# LinearA_2017_4L_1.net
KiCad netlist of a schematic drawn in EAGLE
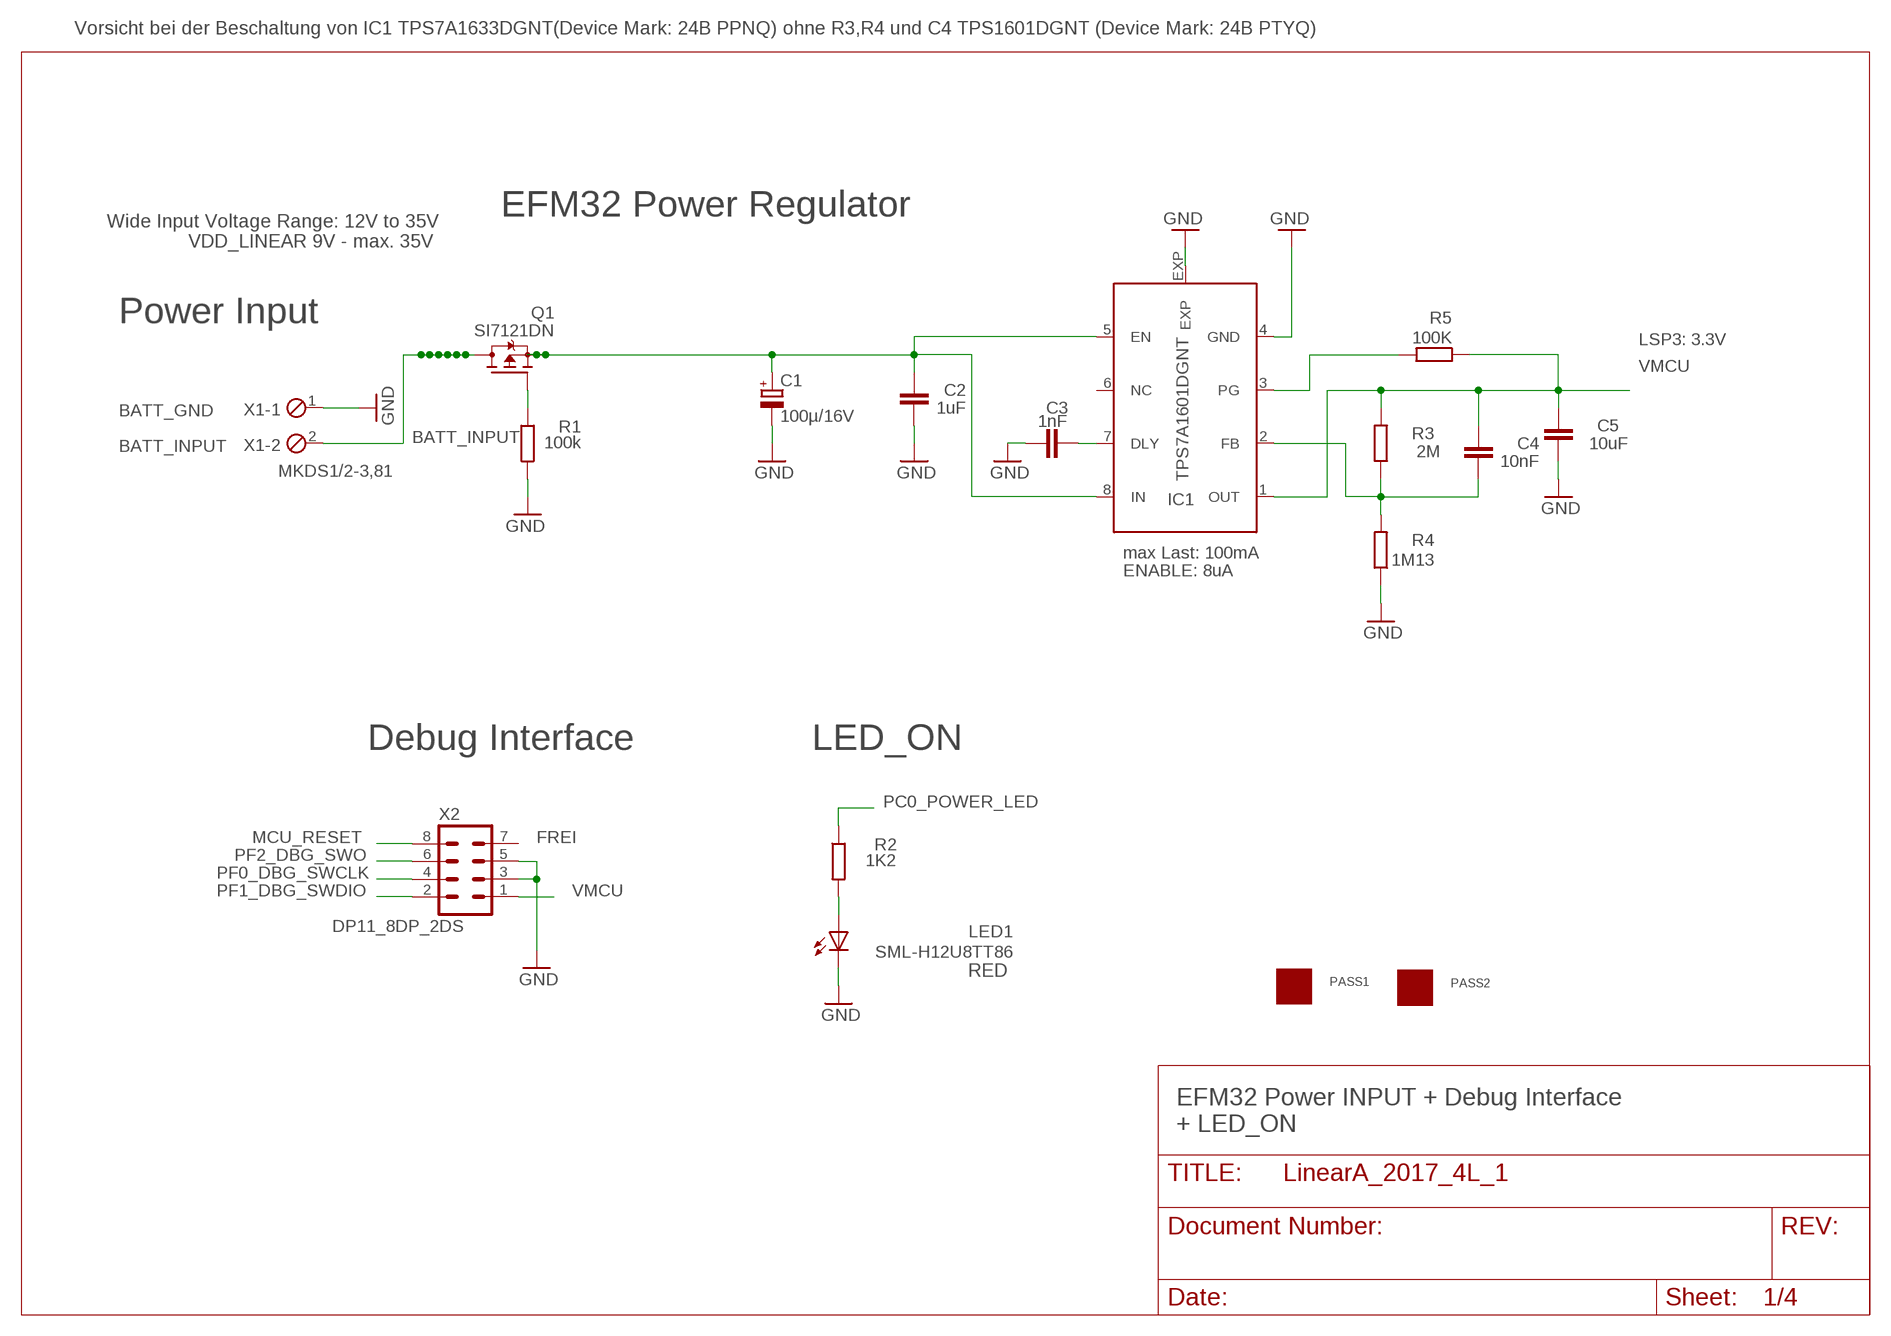
[diagram p0: schematic, sheet 1]
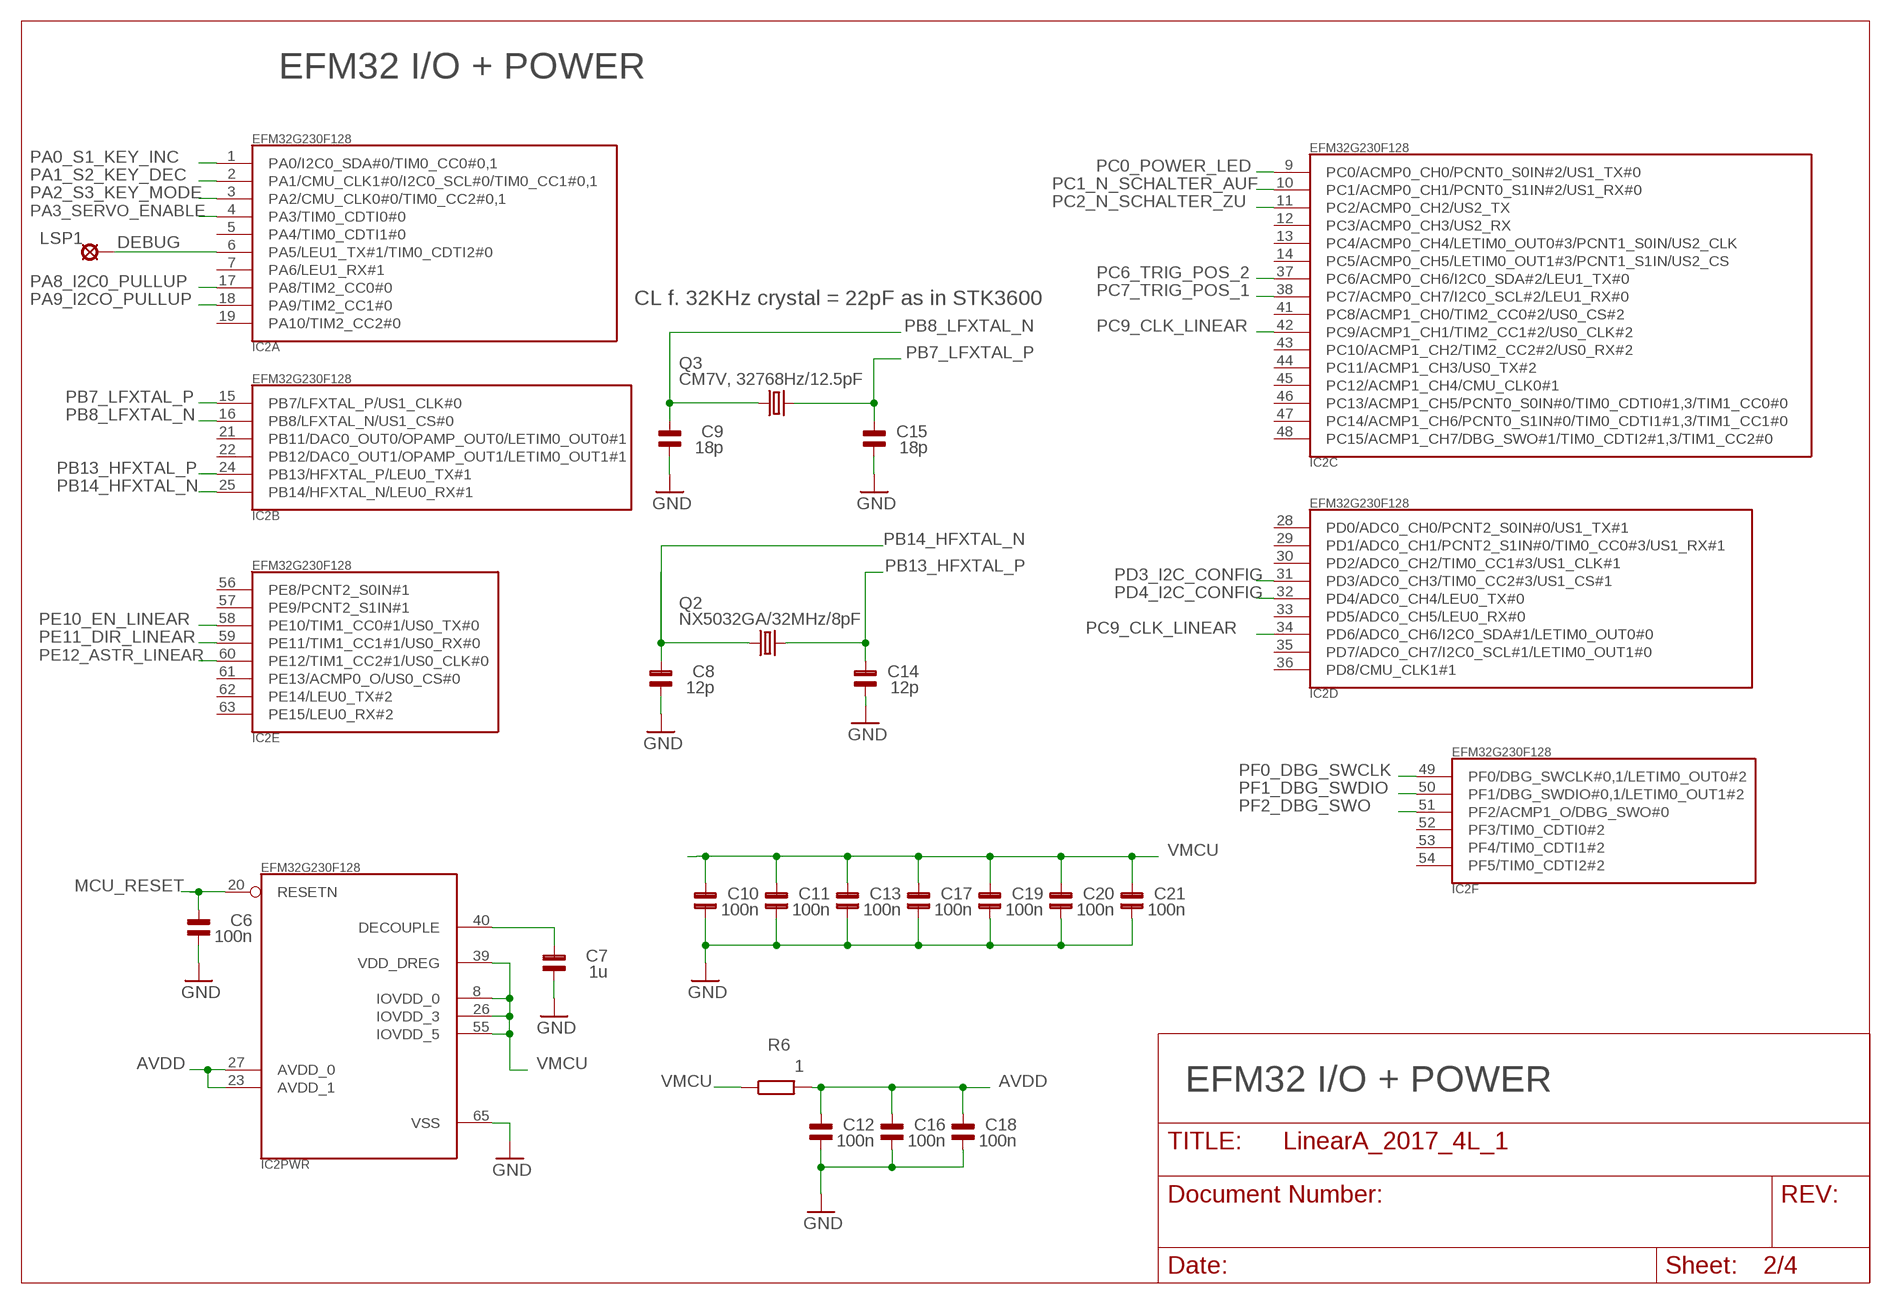
[diagram p1: schematic, sheet 2]
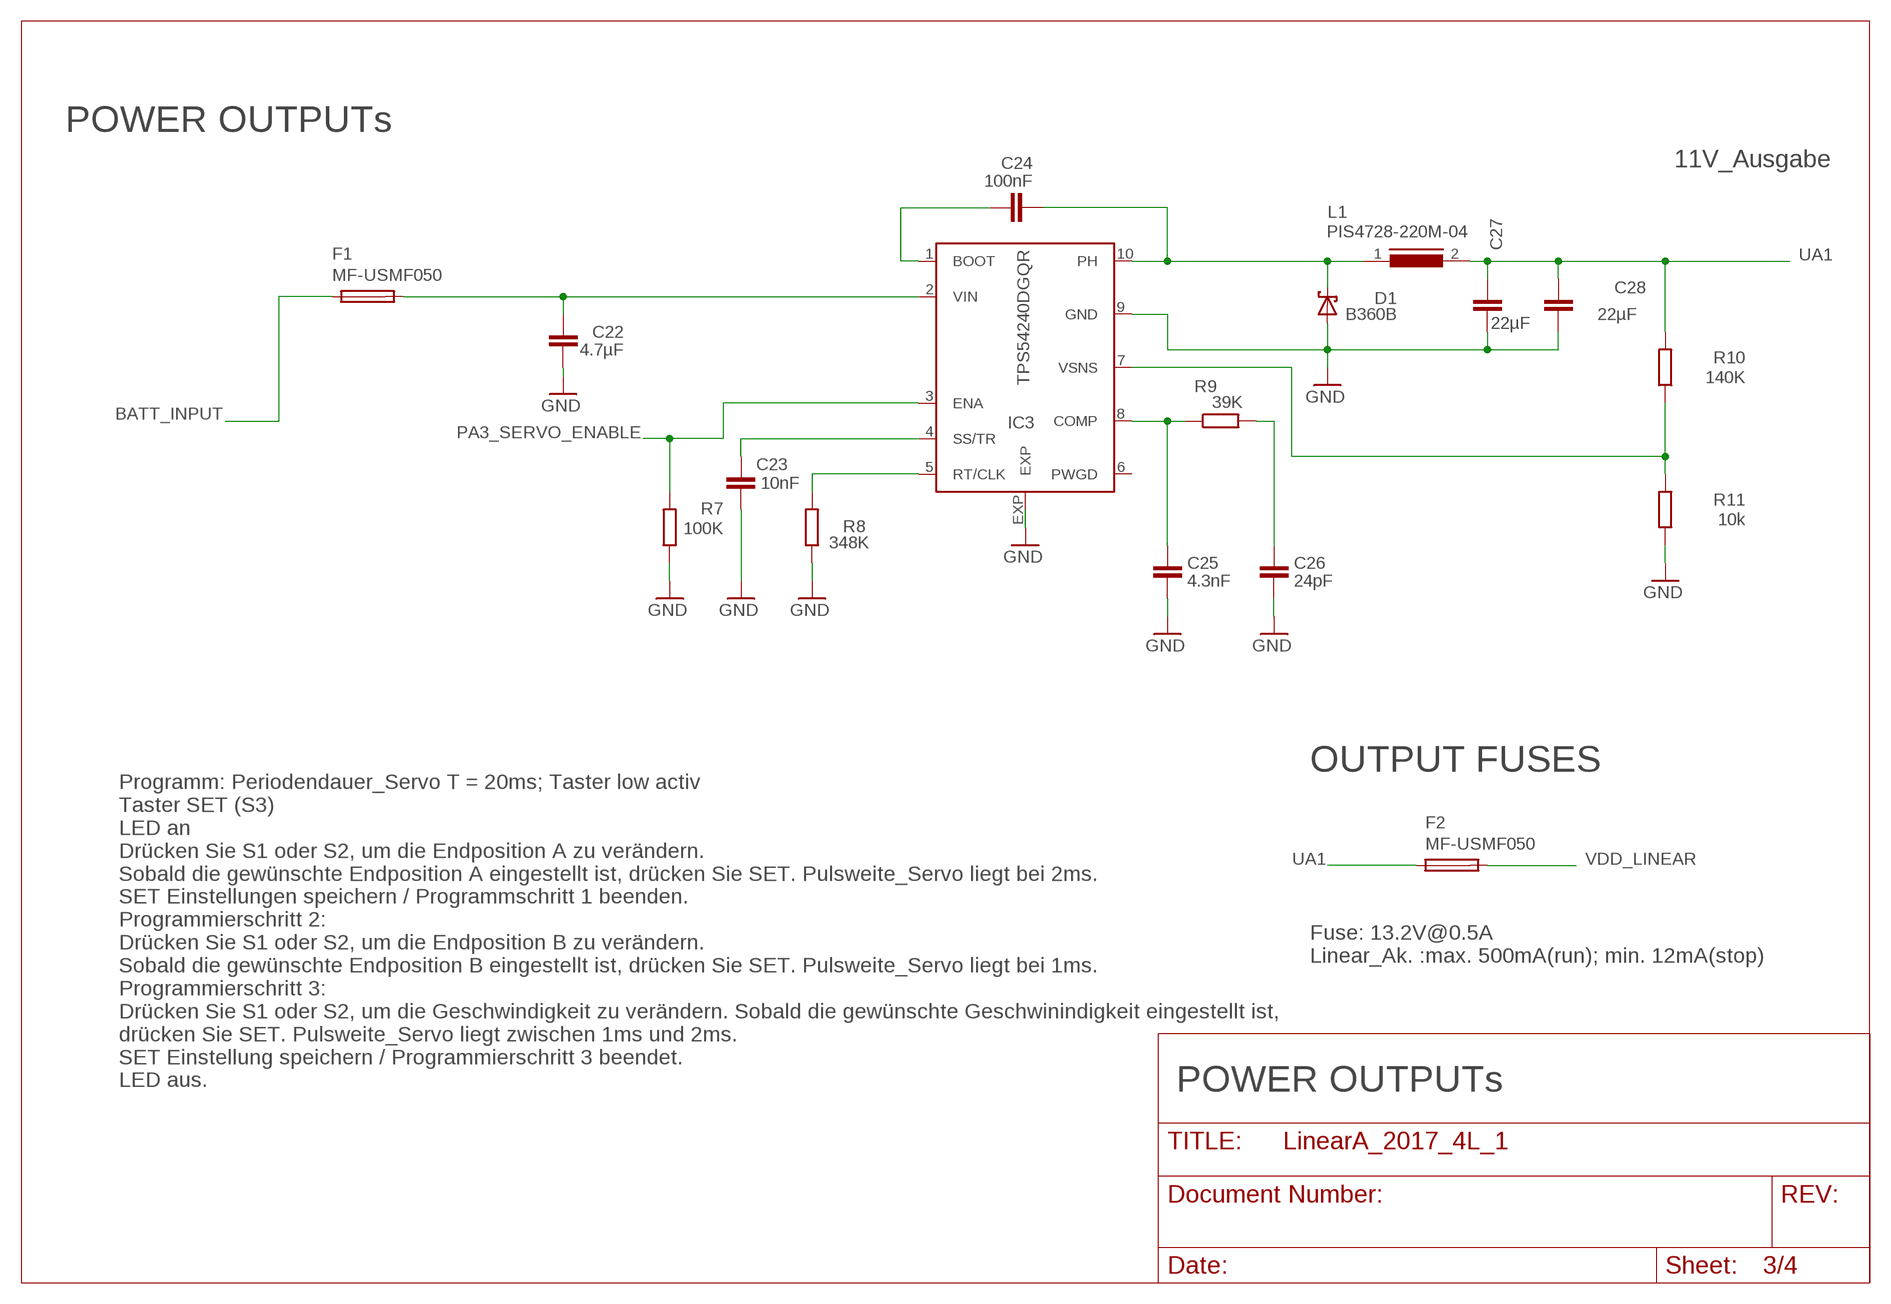
[diagram p2: schematic, sheet 3]
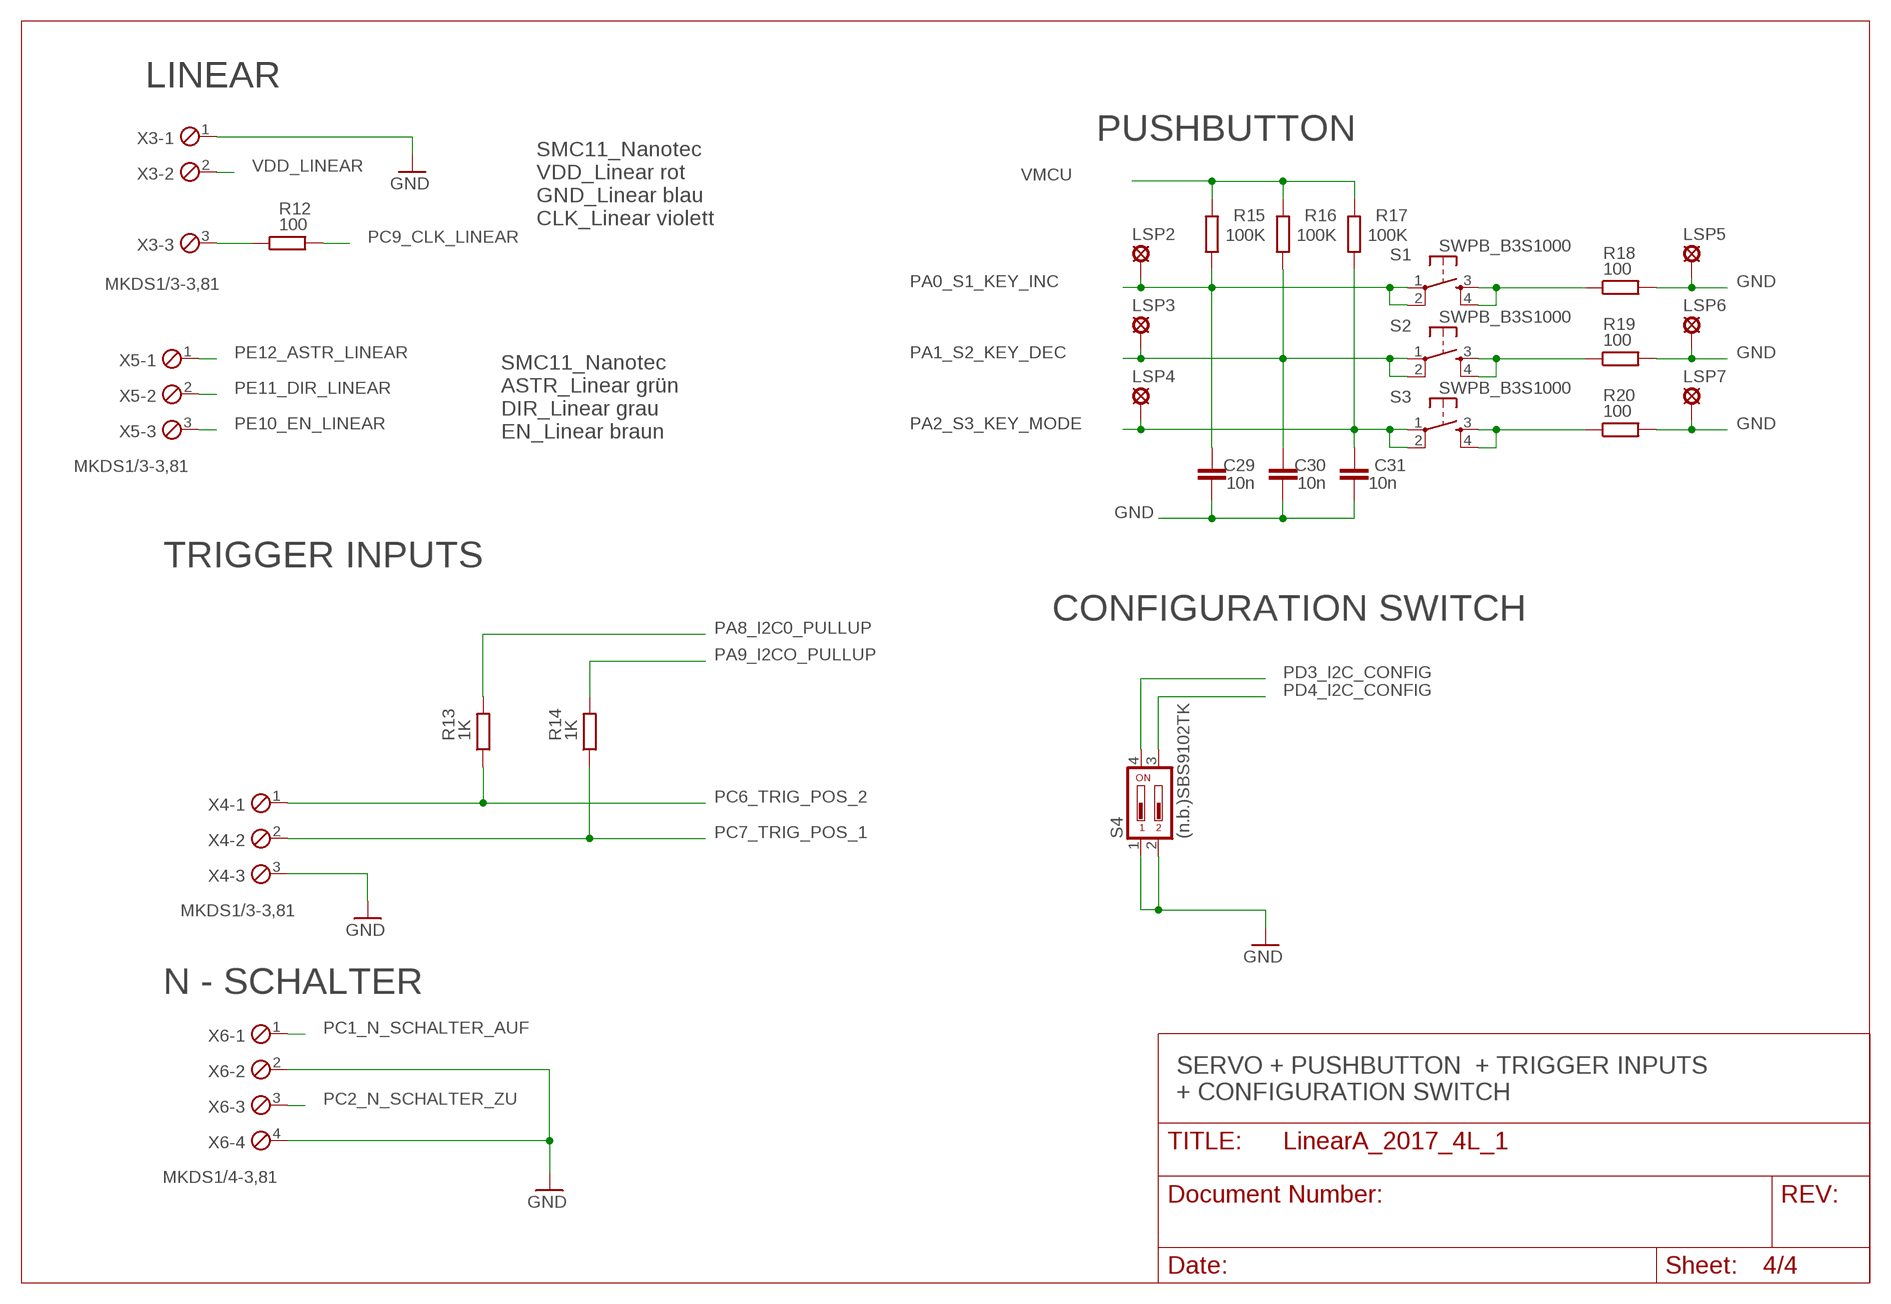
[diagram p3: schematic, sheet 4]

(export (version "E")
  (design (tool "Eeschema 10.0.6"))
  (components
    (comp (ref "C6")
      (value "100n")
      (footprint "eagle-import:0805")
      (libsource (lib "eagle-import") (part "C_SMD0805"))
    )
    (comp (ref "C7")
      (value "1u")
      (footprint "eagle-import:0805")
      (libsource (lib "eagle-import") (part "C_SMD0805"))
    )
    (comp (ref "C8")
      (value "12p")
      (footprint "eagle-import:0805")
      (libsource (lib "eagle-import") (part "C_SMD0805"))
    )
    (comp (ref "C9")
      (value "18p")
      (footprint "eagle-import:0805")
      (libsource (lib "eagle-import") (part "C_SMD0805"))
    )
    (comp (ref "C10")
      (value "100n")
      (footprint "eagle-import:0805")
      (libsource (lib "eagle-import") (part "C_SMD0805"))
    )
    (comp (ref "C11")
      (value "100n")
      (footprint "eagle-import:0805")
      (libsource (lib "eagle-import") (part "C_SMD0805"))
    )
    (comp (ref "C12")
      (value "100n")
      (footprint "eagle-import:0805")
      (libsource (lib "eagle-import") (part "C_SMD0805"))
    )
    (comp (ref "C13")
      (value "100n")
      (footprint "eagle-import:0805")
      (libsource (lib "eagle-import") (part "C_SMD0805"))
    )
    (comp (ref "C14")
      (value "12p")
      (footprint "eagle-import:0805")
      (libsource (lib "eagle-import") (part "C_SMD0805"))
    )
    (comp (ref "C15")
      (value "18p")
      (footprint "eagle-import:0805")
      (libsource (lib "eagle-import") (part "C_SMD0805"))
    )
    (comp (ref "C16")
      (value "100n")
      (footprint "eagle-import:0805")
      (libsource (lib "eagle-import") (part "C_SMD0805"))
    )
    (comp (ref "C17")
      (value "100n")
      (footprint "eagle-import:0805")
      (libsource (lib "eagle-import") (part "C_SMD0805"))
    )
    (comp (ref "C18")
      (value "100n")
      (footprint "eagle-import:0805")
      (libsource (lib "eagle-import") (part "C_SMD0805"))
    )
    (comp (ref "C19")
      (value "100n")
      (footprint "eagle-import:0805")
      (libsource (lib "eagle-import") (part "C_SMD0805"))
    )
    (comp (ref "C20")
      (value "100n")
      (footprint "eagle-import:0805")
      (libsource (lib "eagle-import") (part "C_SMD0805"))
    )
    (comp (ref "C21")
      (value "100n")
      (footprint "eagle-import:0805")
      (libsource (lib "eagle-import") (part "C_SMD0805"))
    )
    (comp (ref "IC2")
      (value "EFM32G230F128")
      (footprint "eagle-import:QFN64")
      (libsource (lib "eagle-import") (part "EFM32G230F128"))
    )
    (comp (ref "LSP1")
      (value "(n.b.)LSP10")
      (footprint "eagle-import:LSP10")
      (libsource (lib "eagle-import") (part "LSP10"))
    )
    (comp (ref "Q2")
      (value "NX5032GA/32MHz/8pF")
      (footprint "eagle-import:CRYSTAL2P5.0X3.2")
      (libsource (lib "eagle-import") (part "CRYSTAL2P5.0X3.2"))
    )
    (comp (ref "Q3")
      (value "CM7V, 32768Hz/12.5pF")
      (footprint "eagle-import:CRYSTAL2P3.2X1.5")
      (libsource (lib "eagle-import") (part "CRYSTAL2P"))
    )
    (comp (ref "R6")
      (value "1")
      (footprint "eagle-import:R0805")
      (libsource (lib "eagle-import") (part "R-EU_R0805"))
    )
    (comp (ref "C29")
      (value "10n")
      (footprint "eagle-import:C0603")
      (libsource (lib "eagle-import") (part "resistor_C-EUC0603"))
    )
    (comp (ref "C30")
      (value "10n")
      (footprint "eagle-import:C0603")
      (libsource (lib "eagle-import") (part "resistor_C-EUC0603"))
    )
    (comp (ref "C31")
      (value "10n")
      (footprint "eagle-import:C0603")
      (libsource (lib "eagle-import") (part "resistor_C-EUC0603"))
    )
    (comp (ref "LSP2")
      (value "(n.b.)LSP10")
      (footprint "eagle-import:LSP10")
      (libsource (lib "eagle-import") (part "LSP10"))
    )
    (comp (ref "LSP3")
      (value "(n.b.)LSP10")
      (footprint "eagle-import:LSP10")
      (libsource (lib "eagle-import") (part "LSP10"))
    )
    (comp (ref "LSP4")
      (value "(n.b.)LSP10")
      (footprint "eagle-import:LSP10")
      (libsource (lib "eagle-import") (part "LSP10"))
    )
    (comp (ref "LSP5")
      (value "(n.b.)LSP10")
      (footprint "eagle-import:LSP10")
      (libsource (lib "eagle-import") (part "LSP10"))
    )
    (comp (ref "LSP6")
      (value "(n.b.)LSP10")
      (footprint "eagle-import:LSP10")
      (libsource (lib "eagle-import") (part "LSP10"))
    )
    (comp (ref "LSP7")
      (value "(n.b.)LSP10")
      (footprint "eagle-import:LSP10")
      (libsource (lib "eagle-import") (part "LSP10"))
    )
    (comp (ref "R12")
      (value "100")
      (footprint "eagle-import:R0805")
      (libsource (lib "eagle-import") (part "resistor_R-EU_R0805"))
    )
    (comp (ref "R13")
      (value "1K")
      (footprint "eagle-import:R0805")
      (libsource (lib "eagle-import") (part "resistor_R-EU_R0805"))
    )
    (comp (ref "R14")
      (value "1K")
      (footprint "eagle-import:R0805")
      (libsource (lib "eagle-import") (part "resistor_R-EU_R0805"))
    )
    (comp (ref "R15")
      (value "100K")
      (footprint "eagle-import:R0805")
      (libsource (lib "eagle-import") (part "resistor_R-EU_R0805"))
    )
    (comp (ref "R16")
      (value "100K")
      (footprint "eagle-import:R0805")
      (libsource (lib "eagle-import") (part "resistor_R-EU_R0805"))
    )
    (comp (ref "R17")
      (value "100K")
      (footprint "eagle-import:R0805")
      (libsource (lib "eagle-import") (part "resistor_R-EU_R0805"))
    )
    (comp (ref "R18")
      (value "100")
      (footprint "eagle-import:R0805")
      (libsource (lib "eagle-import") (part "resistor_R-EU_R0805"))
    )
    (comp (ref "R19")
      (value "100")
      (footprint "eagle-import:R0805")
      (libsource (lib "eagle-import") (part "resistor_R-EU_R0805"))
    )
    (comp (ref "R20")
      (value "100")
      (footprint "eagle-import:R0805")
      (libsource (lib "eagle-import") (part "resistor_R-EU_R0805"))
    )
    (comp (ref "S1")
      (value "SWPB_B3S1000")
      (footprint "eagle-import:DTSM-6")
      (libsource (lib "eagle-import") (part "DTSM-6"))
    )
    (comp (ref "S2")
      (value "SWPB_B3S1000")
      (footprint "eagle-import:DTSM-6")
      (libsource (lib "eagle-import") (part "DTSM-6"))
    )
    (comp (ref "S3")
      (value "SWPB_B3S1000")
      (footprint "eagle-import:DTSM-6")
      (libsource (lib "eagle-import") (part "DTSM-6"))
    )
    (comp (ref "S4")
      (value "(n.b.)SBS9102TK")
      (footprint "eagle-import:CTS-219-02")
      (libsource (lib "eagle-import") (part "219-02"))
    )
    (comp (ref "X3")
      (value "MKDS1/3-3,81")
      (footprint "eagle-import:3POL381")
      (libsource (lib "eagle-import") (part "MKDS1/3-3,81"))
    )
    (comp (ref "X4")
      (value "MKDS1/3-3,81")
      (footprint "eagle-import:3POL381")
      (libsource (lib "eagle-import") (part "MKDS1/3-3,81"))
    )
    (comp (ref "X5")
      (value "MKDS1/3-3,81")
      (footprint "eagle-import:3POL381")
      (libsource (lib "eagle-import") (part "MKDS1/3-3,81"))
    )
    (comp (ref "X6")
      (value "MKDS1/4-3,81")
      (footprint "eagle-import:4POL381")
      (libsource (lib "eagle-import") (part "MKDS1/4-3,81"))
    )
    (comp (ref "C22")
      (value "4.7µF")
      (footprint "eagle-import:C1210")
      (libsource (lib "eagle-import") (part "C-EUC1210"))
    )
    (comp (ref "C23")
      (value "10nF")
      (footprint "eagle-import:C0603")
      (libsource (lib "eagle-import") (part "C-EUC0603"))
    )
    (comp (ref "C24")
      (value "100nF")
      (footprint "eagle-import:C0603")
      (libsource (lib "eagle-import") (part "C-EUC0603"))
    )
    (comp (ref "C25")
      (value "4.3nF")
      (footprint "eagle-import:C0603")
      (libsource (lib "eagle-import") (part "C-EUC0603"))
    )
    (comp (ref "C26")
      (value "24pF")
      (footprint "eagle-import:C0603")
      (libsource (lib "eagle-import") (part "C-EUC0603"))
    )
    (comp (ref "C27")
      (value "22µF")
      (footprint "eagle-import:C1210")
      (libsource (lib "eagle-import") (part "C-EUC1210"))
    )
    (comp (ref "C28")
      (value "22µF")
      (footprint "eagle-import:C1210")
      (libsource (lib "eagle-import") (part "C-EUC1210"))
    )
    (comp (ref "D1")
      (value "B360B")
      (footprint "eagle-import:SMB")
      (libsource (lib "eagle-import") (part "SCHOTTKY-DIODESMD"))
    )
    (comp (ref "F1")
      (value "MF-USMF050")
      (footprint "eagle-import:PFUF_1210POLY")
      (libsource (lib "eagle-import") (part "PFUF"))
    )
    (comp (ref "F2")
      (value "MF-USMF050")
      (footprint "eagle-import:PFUF_1210POLY")
      (libsource (lib "eagle-import") (part "PFUF"))
    )
    (comp (ref "IC3")
      (value "TPS54240DGQR")
      (footprint "eagle-import:S-PDSO-G10")
      (libsource (lib "eagle-import") (part "TPS54240DGQR"))
    )
    (comp (ref "L1")
      (value "PIS4728-220M-04")
      (footprint "eagle-import:DR127")
      (libsource (lib "eagle-import") (part "DR127"))
    )
    (comp (ref "R7")
      (value "100K")
      (footprint "eagle-import:R0805")
      (libsource (lib "eagle-import") (part "resistor_R-EU_R0805"))
    )
    (comp (ref "R8")
      (value "348K")
      (footprint "eagle-import:R0805")
      (libsource (lib "eagle-import") (part "resistor_R-EU_R0805"))
    )
    (comp (ref "R9")
      (value "39K")
      (footprint "eagle-import:R0805")
      (libsource (lib "eagle-import") (part "resistor_R-EU_R0805"))
    )
    (comp (ref "R10")
      (value "140K")
      (footprint "eagle-import:R0805")
      (libsource (lib "eagle-import") (part "resistor_R-EU_R0805"))
    )
    (comp (ref "R11")
      (value "10k")
      (footprint "eagle-import:R0805")
      (libsource (lib "eagle-import") (part "resistor_R-EU_R0805"))
    )
    (comp (ref "C1")
      (value "100µ/16V")
      (footprint "eagle-import:PANASONIC_E")
      (libsource (lib "eagle-import") (part "CPOL-EUE"))
    )
    (comp (ref "C2")
      (value "1uF")
      (footprint "eagle-import:C0603")
      (libsource (lib "eagle-import") (part "resistor_C-EUC0603"))
    )
    (comp (ref "C3")
      (value "1nF")
      (footprint "eagle-import:C0603")
      (libsource (lib "eagle-import") (part "resistor_C-EUC0603"))
    )
    (comp (ref "C4")
      (value "10nF")
      (footprint "eagle-import:C0603")
      (libsource (lib "eagle-import") (part "resistor_C-EUC0603"))
    )
    (comp (ref "C5")
      (value "10uF")
      (footprint "eagle-import:C1206")
      (libsource (lib "eagle-import") (part "resistor_C-EUC1206"))
    )
    (comp (ref "IC1")
      (value "TPS7A1601DGNT")
      (footprint "eagle-import:DGN_S-PDSO-G8-EXP")
      (libsource (lib "eagle-import") (part "TPS7A16"))
    )
    (comp (ref "LED1")
      (value "SML-H12U8TT86")
      (footprint "eagle-import:CHIPLED_0805")
      (libsource (lib "eagle-import") (part "LEDCHIPLED_0805"))
    )
    (comp (ref "PASS1")
      (value "ROUND_1MM1.5")
      (footprint "eagle-import:ROUND2_1.5MM")
      (libsource (lib "eagle-import") (part "ROUND_1MM1.5"))
    )
    (comp (ref "PASS2")
      (value "ROUND_1MM1.5")
      (footprint "eagle-import:ROUND2_1.5MM")
      (libsource (lib "eagle-import") (part "ROUND_1MM1.5"))
    )
    (comp (ref "Q1")
      (value "SI7121DN")
      (footprint "eagle-import:TRANSISTOR-FET_1212-8S")
      (libsource (lib "eagle-import") (part "TRANSISTOR-FET_SI7113DN"))
    )
    (comp (ref "R1")
      (value "100k")
      (footprint "eagle-import:R0805")
      (libsource (lib "eagle-import") (part "resistor_R-EU_R0805"))
    )
    (comp (ref "R2")
      (value "1K2")
      (footprint "eagle-import:R0805")
      (libsource (lib "eagle-import") (part "resistor_R-EU_R0805"))
    )
    (comp (ref "R3")
      (value "2M")
      (footprint "eagle-import:R0805")
      (libsource (lib "eagle-import") (part "resistor_R-EU_R0805"))
    )
    (comp (ref "R4")
      (value "1M13")
      (footprint "eagle-import:R0805")
      (libsource (lib "eagle-import") (part "resistor_R-EU_R0805"))
    )
    (comp (ref "R5")
      (value "100K")
      (footprint "eagle-import:R0805")
      (libsource (lib "eagle-import") (part "resistor_R-EU_R0805"))
    )
    (comp (ref "X1")
      (value "MKDS1/2-3,81")
      (footprint "eagle-import:2POL381")
      (libsource (lib "eagle-import") (part "MKDS1/2-3,81"))
    )
    (comp (ref "X2")
      (value "DP11_8DP_2DS")
      (footprint "eagle-import:DP11_8DP-2DS")
      (libsource (lib "eagle-import") (part "DP11_8DP_2DS"))
    )
  )
  (nets
    (net (code "1") (name "AVDD") (class "Default")
      (node (ref "C12") (pin "2") (pinfunction "2_2") (pintype "passive"))
      (node (ref "C16") (pin "2") (pinfunction "2_2") (pintype "passive"))
      (node (ref "C18") (pin "2") (pinfunction "2_2") (pintype "passive"))
      (node (ref "IC2") (pin "23") (pinfunction "AVDD_1_23") (pintype "power_in"))
      (node (ref "IC2") (pin "27") (pinfunction "AVDD_0_27") (pintype "power_in"))
      (node (ref "R6") (pin "2") (pinfunction "2_2") (pintype "passive"))
    )
    (net (code "2") (name "BATT_INPUT") (class "Default")
      (node (ref "F1") (pin "P$1") (pinfunction "1_P$1") (pintype "passive"))
      (node (ref "Q1") (pin "10") (pinfunction "D_10") (pintype "passive"))
      (node (ref "Q1") (pin "11") (pinfunction "D_11") (pintype "passive"))
      (node (ref "Q1") (pin "5") (pinfunction "D_5") (pintype "passive"))
      (node (ref "Q1") (pin "6") (pinfunction "D_6") (pintype "passive"))
      (node (ref "Q1") (pin "7") (pinfunction "D_7") (pintype "passive"))
      (node (ref "Q1") (pin "8") (pinfunction "D_8") (pintype "passive"))
      (node (ref "Q1") (pin "9") (pinfunction "D_9") (pintype "passive"))
      (node (ref "X1") (pin "2") (pinfunction "1_2") (pintype "passive"))
    )
    (net (code "3") (name "DEBUG") (class "Default")
      (node (ref "IC2") (pin "6") (pinfunction "PA5/LEU1_TX#1/TIM0_CDTI2#0_6") (pintype "bidirectional"))
      (node (ref "LSP1") (pin "MP") (pinfunction "MP_MP") (pintype "passive"))
    )
    (net (code "4") (name "GND") (class "Default")
      (node (ref "C1") (pin "-") (pinfunction "-_-") (pintype "passive"))
      (node (ref "C10") (pin "1") (pinfunction "1_1") (pintype "passive"))
      (node (ref "C11") (pin "1") (pinfunction "1_1") (pintype "passive"))
      (node (ref "C12") (pin "1") (pinfunction "1_1") (pintype "passive"))
      (node (ref "C13") (pin "1") (pinfunction "1_1") (pintype "passive"))
      (node (ref "C14") (pin "1") (pinfunction "1_1") (pintype "passive"))
      (node (ref "C15") (pin "1") (pinfunction "1_1") (pintype "passive"))
      (node (ref "C16") (pin "1") (pinfunction "1_1") (pintype "passive"))
      (node (ref "C17") (pin "1") (pinfunction "1_1") (pintype "passive"))
      (node (ref "C18") (pin "1") (pinfunction "1_1") (pintype "passive"))
      (node (ref "C19") (pin "1") (pinfunction "1_1") (pintype "passive"))
      (node (ref "C2") (pin "1") (pinfunction "1_1") (pintype "passive"))
      (node (ref "C20") (pin "1") (pinfunction "1_1") (pintype "passive"))
      (node (ref "C21") (pin "1") (pinfunction "1_1") (pintype "passive"))
      (node (ref "C22") (pin "2") (pinfunction "2_2") (pintype "passive"))
      (node (ref "C23") (pin "2") (pinfunction "2_2") (pintype "passive"))
      (node (ref "C25") (pin "2") (pinfunction "2_2") (pintype "passive"))
      (node (ref "C26") (pin "2") (pinfunction "2_2") (pintype "passive"))
      (node (ref "C27") (pin "2") (pinfunction "2_2") (pintype "passive"))
      (node (ref "C28") (pin "2") (pinfunction "2_2") (pintype "passive"))
      (node (ref "C29") (pin "1") (pinfunction "1_1") (pintype "passive"))
      (node (ref "C3") (pin "1") (pinfunction "1_1") (pintype "passive"))
      (node (ref "C30") (pin "1") (pinfunction "1_1") (pintype "passive"))
      (node (ref "C31") (pin "1") (pinfunction "1_1") (pintype "passive"))
      (node (ref "C5") (pin "1") (pinfunction "1_1") (pintype "passive"))
      (node (ref "C6") (pin "1") (pinfunction "1_1") (pintype "passive"))
      (node (ref "C7") (pin "1") (pinfunction "1_1") (pintype "passive"))
      (node (ref "C8") (pin "1") (pinfunction "1_1") (pintype "passive"))
      (node (ref "C9") (pin "1") (pinfunction "1_1") (pintype "passive"))
      (node (ref "D1") (pin "A") (pinfunction "A_A") (pintype "passive"))
      (node (ref "IC1") (pin "4") (pinfunction "GND_4") (pintype "passive"))
      (node (ref "IC1") (pin "EXP") (pinfunction "EXP_EXP") (pintype "passive"))
      (node (ref "IC2") (pin "65") (pinfunction "VSS_65") (pintype "power_in"))
      (node (ref "IC3") (pin "9") (pinfunction "GND_9") (pintype "power_in"))
      (node (ref "IC3") (pin "EXP") (pinfunction "EXP_EXP") (pintype "power_in"))
      (node (ref "LED1") (pin "C") (pinfunction "C_C") (pintype "passive"))
      (node (ref "LSP5") (pin "MP") (pinfunction "MP_MP") (pintype "passive"))
      (node (ref "LSP6") (pin "MP") (pinfunction "MP_MP") (pintype "passive"))
      (node (ref "LSP7") (pin "MP") (pinfunction "MP_MP") (pintype "passive"))
      (node (ref "R1") (pin "1") (pinfunction "1_1") (pintype "passive"))
      (node (ref "R11") (pin "1") (pinfunction "1_1") (pintype "passive"))
      (node (ref "R18") (pin "2") (pinfunction "2_2") (pintype "passive"))
      (node (ref "R19") (pin "2") (pinfunction "2_2") (pintype "passive"))
      (node (ref "R20") (pin "2") (pinfunction "2_2") (pintype "passive"))
      (node (ref "R4") (pin "1") (pinfunction "1_1") (pintype "passive"))
      (node (ref "R7") (pin "1") (pinfunction "1_1") (pintype "passive"))
      (node (ref "R8") (pin "1") (pinfunction "1_1") (pintype "passive"))
      (node (ref "S4") (pin "1") (pinfunction "1_1") (pintype "passive"))
      (node (ref "S4") (pin "2") (pinfunction "2_2") (pintype "passive"))
      (node (ref "X1") (pin "1") (pinfunction "1_1") (pintype "passive"))
      (node (ref "X2") (pin "3") (pinfunction "3_3") (pintype "passive"))
      (node (ref "X2") (pin "5") (pinfunction "5_5") (pintype "passive"))
      (node (ref "X3") (pin "1") (pinfunction "1_1") (pintype "passive"))
      (node (ref "X4") (pin "3") (pinfunction "1_3") (pintype "passive"))
      (node (ref "X6") (pin "2") (pinfunction "1_2") (pintype "passive"))
      (node (ref "X6") (pin "4") (pinfunction "1_4") (pintype "passive"))
    )
    (net (code "5") (name "MCU_RESET") (class "Default")
      (node (ref "C6") (pin "2") (pinfunction "2_2") (pintype "passive"))
      (node (ref "IC2") (pin "20") (pinfunction "RESETN_20") (pintype "passive"))
      (node (ref "X2") (pin "8") (pinfunction "8_8") (pintype "passive"))
    )
    (net (code "6") (name "Net-(C26-Pad1)") (class "Default")
      (node (ref "C26") (pin "1") (pinfunction "1_1") (pintype "passive"))
      (node (ref "R9") (pin "2") (pinfunction "2_2") (pintype "passive"))
    )
    (net (code "7") (name "Net-(F1-2)") (class "Default")
      (node (ref "C22") (pin "1") (pinfunction "1_1") (pintype "passive"))
      (node (ref "F1") (pin "P$2") (pinfunction "2_P$2") (pintype "passive"))
      (node (ref "IC3") (pin "2") (pinfunction "VIN_2") (pintype "input"))
    )
    (net (code "8") (name "Net-(IC1-DLY)") (class "Default")
      (node (ref "C3") (pin "2") (pinfunction "2_2") (pintype "passive"))
      (node (ref "IC1") (pin "7") (pinfunction "DLY_7") (pintype "output"))
    )
    (net (code "9") (name "Net-(IC1-EN)") (class "Default")
      (node (ref "C1") (pin "+") (pinfunction "+_+") (pintype "passive"))
      (node (ref "C2") (pin "2") (pinfunction "2_2") (pintype "passive"))
      (node (ref "IC1") (pin "5") (pinfunction "EN_5") (pintype "input"))
      (node (ref "IC1") (pin "8") (pinfunction "IN_8") (pintype "passive"))
      (node (ref "Q1") (pin "1") (pinfunction "S_1") (pintype "passive"))
      (node (ref "Q1") (pin "2") (pinfunction "S_2") (pintype "passive"))
      (node (ref "Q1") (pin "3") (pinfunction "S_3") (pintype "passive"))
    )
    (net (code "10") (name "Net-(IC1-FB)") (class "Default")
      (node (ref "C4") (pin "1") (pinfunction "1_1") (pintype "passive"))
      (node (ref "IC1") (pin "2") (pinfunction "FB_2") (pintype "input"))
      (node (ref "R3") (pin "1") (pinfunction "1_1") (pintype "passive"))
      (node (ref "R4") (pin "2") (pinfunction "2_2") (pintype "passive"))
    )
    (net (code "11") (name "Net-(IC1-PG)") (class "Default")
      (node (ref "IC1") (pin "3") (pinfunction "PG_3") (pintype "output"))
      (node (ref "R5") (pin "2") (pinfunction "2_2") (pintype "passive"))
    )
    (net (code "12") (name "Net-(IC2G-DECOUPLE)") (class "Default")
      (node (ref "C7") (pin "2") (pinfunction "2_2") (pintype "passive"))
      (node (ref "IC2") (pin "40") (pinfunction "DECOUPLE_40") (pintype "power_in"))
    )
    (net (code "13") (name "Net-(IC3-BOOT)") (class "Default")
      (node (ref "C24") (pin "2") (pinfunction "2_2") (pintype "passive"))
      (node (ref "IC3") (pin "1") (pinfunction "BOOT_1") (pintype "output"))
    )
    (net (code "14") (name "Net-(IC3-COMP)") (class "Default")
      (node (ref "C25") (pin "1") (pinfunction "1_1") (pintype "passive"))
      (node (ref "IC3") (pin "8") (pinfunction "COMP_8") (pintype "input"))
      (node (ref "R9") (pin "1") (pinfunction "1_1") (pintype "passive"))
    )
    (net (code "15") (name "Net-(IC3-PH)") (class "Default")
      (node (ref "C24") (pin "1") (pinfunction "1_1") (pintype "passive"))
      (node (ref "D1") (pin "C") (pinfunction "C_C") (pintype "passive"))
      (node (ref "IC3") (pin "10") (pinfunction "PH_10") (pintype "output"))
      (node (ref "L1") (pin "1") (pinfunction "1_1") (pintype "passive"))
    )
    (net (code "16") (name "Net-(IC3-RT{slash}CLK)") (class "Default")
      (node (ref "IC3") (pin "5") (pinfunction "RT/CLK_5") (pintype "input"))
      (node (ref "R8") (pin "2") (pinfunction "2_2") (pintype "passive"))
    )
    (net (code "17") (name "Net-(IC3-SS{slash}TR)") (class "Default")
      (node (ref "C23") (pin "1") (pinfunction "1_1") (pintype "passive"))
      (node (ref "IC3") (pin "4") (pinfunction "SS/TR_4") (pintype "input"))
    )
    (net (code "18") (name "Net-(IC3-VSNS)") (class "Default")
      (node (ref "IC3") (pin "7") (pinfunction "VSNS_7") (pintype "input"))
      (node (ref "R10") (pin "1") (pinfunction "1_1") (pintype "passive"))
      (node (ref "R11") (pin "2") (pinfunction "2_2") (pintype "passive"))
    )
    (net (code "19") (name "Net-(LED1-PadA)") (class "Default")
      (node (ref "LED1") (pin "A") (pinfunction "A_A") (pintype "passive"))
      (node (ref "R2") (pin "2") (pinfunction "2_2") (pintype "passive"))
    )
    (net (code "20") (name "Net-(Q1-G)") (class "Default")
      (node (ref "Q1") (pin "4") (pinfunction "G_4") (pintype "passive"))
      (node (ref "R1") (pin "2") (pinfunction "2_2") (pintype "passive"))
    )
    (net (code "21") (name "Net-(R18-Pad1)") (class "Default")
      (node (ref "R18") (pin "1") (pinfunction "1_1") (pintype "passive"))
      (node (ref "S1") (pin "3") (pinfunction "3_3") (pintype "passive"))
      (node (ref "S1") (pin "4") (pinfunction "4_4") (pintype "passive"))
    )
    (net (code "22") (name "Net-(R19-Pad1)") (class "Default")
      (node (ref "R19") (pin "1") (pinfunction "1_1") (pintype "passive"))
      (node (ref "S2") (pin "3") (pinfunction "3_3") (pintype "passive"))
      (node (ref "S2") (pin "4") (pinfunction "4_4") (pintype "passive"))
    )
    (net (code "23") (name "Net-(R20-Pad1)") (class "Default")
      (node (ref "R20") (pin "1") (pinfunction "1_1") (pintype "passive"))
      (node (ref "S3") (pin "3") (pinfunction "3_3") (pintype "passive"))
      (node (ref "S3") (pin "4") (pinfunction "4_4") (pintype "passive"))
    )
    (net (code "24") (name "Net-(X3C-1)") (class "Default")
      (node (ref "R12") (pin "1") (pinfunction "1_1") (pintype "passive"))
      (node (ref "X3") (pin "3") (pinfunction "1_3") (pintype "passive"))
    )
    (net (code "25") (name "PA0_S1_KEY_INC") (class "Default")
      (node (ref "C29") (pin "2") (pinfunction "2_2") (pintype "passive"))
      (node (ref "IC2") (pin "1") (pinfunction "PA0/I2C0_SDA#0/TIM0_CC0#0,1_1") (pintype "bidirectional"))
      (node (ref "LSP2") (pin "MP") (pinfunction "MP_MP") (pintype "passive"))
      (node (ref "R15") (pin "1") (pinfunction "1_1") (pintype "passive"))
      (node (ref "S1") (pin "1") (pinfunction "1_1") (pintype "passive"))
      (node (ref "S1") (pin "2") (pinfunction "2_2") (pintype "passive"))
    )
    (net (code "26") (name "PA1_S2_KEY_DEC") (class "Default")
      (node (ref "C30") (pin "2") (pinfunction "2_2") (pintype "passive"))
      (node (ref "IC2") (pin "2") (pinfunction "PA1/CMU_CLK1#0/I2C0_SCL#0/TIM0_CC1#0,1_2") (pintype "bidirectional"))
      (node (ref "LSP3") (pin "MP") (pinfunction "MP_MP") (pintype "passive"))
      (node (ref "R16") (pin "1") (pinfunction "1_1") (pintype "passive"))
      (node (ref "S2") (pin "1") (pinfunction "1_1") (pintype "passive"))
      (node (ref "S2") (pin "2") (pinfunction "2_2") (pintype "passive"))
    )
    (net (code "27") (name "PA2_S3_KEY_MODE") (class "Default")
      (node (ref "C31") (pin "2") (pinfunction "2_2") (pintype "passive"))
      (node (ref "IC2") (pin "3") (pinfunction "PA2/CMU_CLK0#0/TIM0_CC2#0,1_3") (pintype "bidirectional"))
      (node (ref "LSP4") (pin "MP") (pinfunction "MP_MP") (pintype "passive"))
      (node (ref "R17") (pin "1") (pinfunction "1_1") (pintype "passive"))
      (node (ref "S3") (pin "1") (pinfunction "1_1") (pintype "passive"))
      (node (ref "S3") (pin "2") (pinfunction "2_2") (pintype "passive"))
    )
    (net (code "28") (name "PA3_SERVO_ENABLE") (class "Default")
      (node (ref "IC2") (pin "4") (pinfunction "PA3/TIM0_CDTI0#0_4") (pintype "bidirectional"))
      (node (ref "IC3") (pin "3") (pinfunction "ENA_3") (pintype "input"))
      (node (ref "R7") (pin "2") (pinfunction "2_2") (pintype "passive"))
    )
    (net (code "29") (name "PA8_I2C0_PULLUP") (class "Default")
      (node (ref "IC2") (pin "17") (pinfunction "PA8/TIM2_CC0#0_17") (pintype "bidirectional"))
      (node (ref "R13") (pin "2") (pinfunction "2_2") (pintype "passive"))
    )
    (net (code "30") (name "PA9_I2CO_PULLUP") (class "Default")
      (node (ref "IC2") (pin "18") (pinfunction "PA9/TIM2_CC1#0_18") (pintype "bidirectional"))
      (node (ref "R14") (pin "2") (pinfunction "2_2") (pintype "passive"))
    )
    (net (code "31") (name "PB7_LFXTAL_P") (class "Default")
      (node (ref "C15") (pin "2") (pinfunction "2_2") (pintype "passive"))
      (node (ref "IC2") (pin "15") (pinfunction "PB7/LFXTAL_P/US1_CLK#0_15") (pintype "bidirectional"))
      (node (ref "Q3") (pin "2") (pinfunction "2_2") (pintype "passive"))
    )
    (net (code "32") (name "PB8_LFXTAL_N") (class "Default")
      (node (ref "C9") (pin "2") (pinfunction "2_2") (pintype "passive"))
      (node (ref "IC2") (pin "16") (pinfunction "PB8/LFXTAL_N/US1_CS#0_16") (pintype "bidirectional"))
      (node (ref "Q3") (pin "1") (pinfunction "1_1") (pintype "passive"))
    )
    (net (code "33") (name "PB13_HFXTAL_P") (class "Default")
      (node (ref "C14") (pin "2") (pinfunction "2_2") (pintype "passive"))
      (node (ref "IC2") (pin "24") (pinfunction "PB13/HFXTAL_P/LEU0_TX#1_24") (pintype "bidirectional"))
      (node (ref "Q2") (pin "2") (pinfunction "2_2") (pintype "passive"))
    )
    (net (code "34") (name "PB14_HFXTAL_N") (class "Default")
      (node (ref "C8") (pin "2") (pinfunction "2_2") (pintype "passive"))
      (node (ref "IC2") (pin "25") (pinfunction "PB14/HFXTAL_N/LEU0_RX#1_25") (pintype "bidirectional"))
      (node (ref "Q2") (pin "1") (pinfunction "1_1") (pintype "passive"))
    )
    (net (code "35") (name "PC0_POWER_LED") (class "Default")
      (node (ref "IC2") (pin "9") (pinfunction "PC0/ACMP0_CH0/PCNT0_S0IN#2/US1_TX#0_9") (pintype "bidirectional"))
      (node (ref "R2") (pin "1") (pinfunction "1_1") (pintype "passive"))
    )
    (net (code "36") (name "PC1_N_SCHALTER_AUF") (class "Default")
      (node (ref "IC2") (pin "10") (pinfunction "PC1/ACMP0_CH1/PCNT0_S1IN#2/US1_RX#0_10") (pintype "bidirectional"))
      (node (ref "X6") (pin "1") (pinfunction "1_1") (pintype "passive"))
    )
    (net (code "37") (name "PC2_N_SCHALTER_ZU") (class "Default")
      (node (ref "IC2") (pin "11") (pinfunction "PC2/ACMP0_CH2/US2_TX_11") (pintype "bidirectional"))
      (node (ref "X6") (pin "3") (pinfunction "1_3") (pintype "passive"))
    )
    (net (code "38") (name "PC6_TRIG_POS_2") (class "Default")
      (node (ref "IC2") (pin "37") (pinfunction "PC6/ACMP0_CH6/I2C0_SDA#2/LEU1_TX#0_37") (pintype "bidirectional"))
      (node (ref "R13") (pin "1") (pinfunction "1_1") (pintype "passive"))
      (node (ref "X4") (pin "1") (pinfunction "1_1") (pintype "passive"))
    )
    (net (code "39") (name "PC7_TRIG_POS_1") (class "Default")
      (node (ref "IC2") (pin "38") (pinfunction "PC7/ACMP0_CH7/I2C0_SCL#2/LEU1_RX#0_38") (pintype "bidirectional"))
      (node (ref "R14") (pin "1") (pinfunction "1_1") (pintype "passive"))
      (node (ref "X4") (pin "2") (pinfunction "1_2") (pintype "passive"))
    )
    (net (code "40") (name "PC9_CLK_LINEAR") (class "Default")
      (node (ref "IC2") (pin "34") (pinfunction "PD6/ADC0_CH6/I2C0_SDA#1/LETIM0_OUT0#0_34") (pintype "bidirectional"))
      (node (ref "IC2") (pin "42") (pinfunction "PC9/ACMP1_CH1/TIM2_CC1#2/US0_CLK#2_42") (pintype "bidirectional"))
      (node (ref "R12") (pin "2") (pinfunction "2_2") (pintype "passive"))
    )
    (net (code "41") (name "PD3_I2C_CONFIG") (class "Default")
      (node (ref "IC2") (pin "31") (pinfunction "PD3/ADC0_CH3/TIM0_CC2#3/US1_CS#1_31") (pintype "bidirectional"))
      (node (ref "S4") (pin "4") (pinfunction "4_4") (pintype "passive"))
    )
    (net (code "42") (name "PD4_I2C_CONFIG") (class "Default")
      (node (ref "IC2") (pin "32") (pinfunction "PD4/ADC0_CH4/LEU0_TX#0_32") (pintype "bidirectional"))
      (node (ref "S4") (pin "3") (pinfunction "3_3") (pintype "passive"))
    )
    (net (code "43") (name "PE10_EN_LINEAR") (class "Default")
      (node (ref "IC2") (pin "58") (pinfunction "PE10/TIM1_CC0#1/US0_TX#0_58") (pintype "bidirectional"))
      (node (ref "X5") (pin "3") (pinfunction "1_3") (pintype "passive"))
    )
    (net (code "44") (name "PE11_DIR_LINEAR") (class "Default")
      (node (ref "IC2") (pin "59") (pinfunction "PE11/TIM1_CC1#1/US0_RX#0_59") (pintype "bidirectional"))
      (node (ref "X5") (pin "2") (pinfunction "1_2") (pintype "passive"))
    )
    (net (code "45") (name "PE12_ASTR_LINEAR") (class "Default")
      (node (ref "IC2") (pin "60") (pinfunction "PE12/TIM1_CC2#1/US0_CLK#0_60") (pintype "bidirectional"))
      (node (ref "X5") (pin "1") (pinfunction "1_1") (pintype "passive"))
    )
    (net (code "46") (name "PF0_DBG_SWCLK") (class "Default")
      (node (ref "IC2") (pin "49") (pinfunction "PF0/DBG_SWCLK#0,1/LETIM0_OUT0#2_49") (pintype "bidirectional"))
      (node (ref "X2") (pin "4") (pinfunction "4_4") (pintype "passive"))
    )
    (net (code "47") (name "PF1_DBG_SWDIO") (class "Default")
      (node (ref "IC2") (pin "50") (pinfunction "PF1/DBG_SWDIO#0,1/LETIM0_OUT1#2_50") (pintype "bidirectional"))
      (node (ref "X2") (pin "2") (pinfunction "2_2") (pintype "passive"))
    )
    (net (code "48") (name "PF2_DBG_SWO") (class "Default")
      (node (ref "IC2") (pin "51") (pinfunction "PF2/ACMP1_O/DBG_SWO#0_51") (pintype "bidirectional"))
      (node (ref "X2") (pin "6") (pinfunction "6_6") (pintype "passive"))
    )
    (net (code "49") (name "UA1") (class "Default")
      (node (ref "C27") (pin "1") (pinfunction "1_1") (pintype "passive"))
      (node (ref "C28") (pin "1") (pinfunction "1_1") (pintype "passive"))
      (node (ref "F2") (pin "P$1") (pinfunction "1_P$1") (pintype "passive"))
      (node (ref "L1") (pin "2") (pinfunction "2_2") (pintype "passive"))
      (node (ref "R10") (pin "2") (pinfunction "2_2") (pintype "passive"))
    )
    (net (code "50") (name "VDD_LINEAR") (class "Default")
      (node (ref "F2") (pin "P$2") (pinfunction "2_P$2") (pintype "passive"))
      (node (ref "X3") (pin "2") (pinfunction "1_2") (pintype "passive"))
    )
    (net (code "51") (name "VMCU") (class "Default")
      (node (ref "C10") (pin "2") (pinfunction "2_2") (pintype "passive"))
      (node (ref "C11") (pin "2") (pinfunction "2_2") (pintype "passive"))
      (node (ref "C13") (pin "2") (pinfunction "2_2") (pintype "passive"))
      (node (ref "C17") (pin "2") (pinfunction "2_2") (pintype "passive"))
      (node (ref "C19") (pin "2") (pinfunction "2_2") (pintype "passive"))
      (node (ref "C20") (pin "2") (pinfunction "2_2") (pintype "passive"))
      (node (ref "C21") (pin "2") (pinfunction "2_2") (pintype "passive"))
      (node (ref "C4") (pin "2") (pinfunction "2_2") (pintype "passive"))
      (node (ref "C5") (pin "2") (pinfunction "2_2") (pintype "passive"))
      (node (ref "IC1") (pin "1") (pinfunction "OUT_1") (pintype "output"))
      (node (ref "IC2") (pin "26") (pinfunction "IOVDD_3_26") (pintype "power_in"))
      (node (ref "IC2") (pin "39") (pinfunction "VDD_DREG_39") (pintype "power_in"))
      (node (ref "IC2") (pin "55") (pinfunction "IOVDD_5_55") (pintype "power_in"))
      (node (ref "IC2") (pin "8") (pinfunction "IOVDD_0_8") (pintype "power_in"))
      (node (ref "R15") (pin "2") (pinfunction "2_2") (pintype "passive"))
      (node (ref "R16") (pin "2") (pinfunction "2_2") (pintype "passive"))
      (node (ref "R17") (pin "2") (pinfunction "2_2") (pintype "passive"))
      (node (ref "R3") (pin "2") (pinfunction "2_2") (pintype "passive"))
      (node (ref "R5") (pin "1") (pinfunction "1_1") (pintype "passive"))
      (node (ref "R6") (pin "1") (pinfunction "1_1") (pintype "passive"))
      (node (ref "X2") (pin "1") (pinfunction "1_1") (pintype "passive"))
    )
    (net (code "52") (name "unconnected-(IC1-NC-Pad6)") (class "Default")
      (node (ref "IC1") (pin "6") (pinfunction "NC_6") (pintype "no_connect"))
    )
    (net (code "53") (name "unconnected-(IC2A-PA4{slash}TIM0_CDTI1#0-Pad5)") (class "Default")
      (node (ref "IC2") (pin "5") (pinfunction "PA4/TIM0_CDTI1#0_5") (pintype "bidirectional"))
    )
    (net (code "54") (name "unconnected-(IC2A-PA6{slash}LEU1_RX#1-Pad7)") (class "Default")
      (node (ref "IC2") (pin "7") (pinfunction "PA6/LEU1_RX#1_7") (pintype "bidirectional"))
    )
    (net (code "55") (name "unconnected-(IC2A-PA10{slash}TIM2_CC2#0-Pad19)") (class "Default")
      (node (ref "IC2") (pin "19") (pinfunction "PA10/TIM2_CC2#0_19") (pintype "bidirectional"))
    )
    (net (code "56") (name "unconnected-(IC2B-PB11{slash}DAC0_OUT0{slash}OPAMP_OUT0{slash}LETIM0_OUT0#1-Pad21)") (class "Default")
      (node (ref "IC2") (pin "21") (pinfunction "PB11/DAC0_OUT0/OPAMP_OUT0/LETIM0_OUT0#1_21") (pintype "bidirectional"))
    )
    (net (code "57") (name "unconnected-(IC2B-PB12{slash}DAC0_OUT1{slash}OPAMP_OUT1{slash}LETIM0_OUT1#1-Pad22)") (class "Default")
      (node (ref "IC2") (pin "22") (pinfunction "PB12/DAC0_OUT1/OPAMP_OUT1/LETIM0_OUT1#1_22") (pintype "bidirectional"))
    )
    (net (code "58") (name "unconnected-(IC2C-PC3{slash}ACMP0_CH3{slash}US2_RX-Pad12)") (class "Default")
      (node (ref "IC2") (pin "12") (pinfunction "PC3/ACMP0_CH3/US2_RX_12") (pintype "bidirectional"))
    )
    (net (code "59") (name "unconnected-(IC2C-PC4{slash}ACMP0_CH4{slash}LETIM0_OUT0#3{slash}PCNT1_S0IN{slash}US2_CLK-Pad13)") (class "Default")
      (node (ref "IC2") (pin "13") (pinfunction "PC4/ACMP0_CH4/LETIM0_OUT0#3/PCNT1_S0IN/US2_CLK_13") (pintype "bidirectional"))
    )
    (net (code "60") (name "unconnected-(IC2C-PC5{slash}ACMP0_CH5{slash}LETIM0_OUT1#3{slash}PCNT1_S1IN{slash}US2_CS-Pad14)") (class "Default")
      (node (ref "IC2") (pin "14") (pinfunction "PC5/ACMP0_CH5/LETIM0_OUT1#3/PCNT1_S1IN/US2_CS_14") (pintype "bidirectional"))
    )
    (net (code "61") (name "unconnected-(IC2C-PC8{slash}ACMP1_CH0{slash}TIM2_CC0#2{slash}US0_CS#2-Pad41)") (class "Default")
      (node (ref "IC2") (pin "41") (pinfunction "PC8/ACMP1_CH0/TIM2_CC0#2/US0_CS#2_41") (pintype "bidirectional"))
    )
    (net (code "62") (name "unconnected-(IC2C-PC10{slash}ACMP1_CH2{slash}TIM2_CC2#2{slash}US0_RX#2-Pad43)") (class "Default")
      (node (ref "IC2") (pin "43") (pinfunction "PC10/ACMP1_CH2/TIM2_CC2#2/US0_RX#2_43") (pintype "bidirectional"))
    )
    (net (code "63") (name "unconnected-(IC2C-PC11{slash}ACMP1_CH3{slash}US0_TX#2-Pad44)") (class "Default")
      (node (ref "IC2") (pin "44") (pinfunction "PC11/ACMP1_CH3/US0_TX#2_44") (pintype "bidirectional"))
    )
    (net (code "64") (name "unconnected-(IC2C-PC12{slash}ACMP1_CH4{slash}CMU_CLK0#1-Pad45)") (class "Default")
      (node (ref "IC2") (pin "45") (pinfunction "PC12/ACMP1_CH4/CMU_CLK0#1_45") (pintype "bidirectional"))
    )
    (net (code "65") (name "unconnected-(IC2C-PC13{slash}ACMP1_CH5{slash}PCNT0_S0IN#0{slash}TIM0_CDTI0#1,3{slash}TIM1_CC0#0-Pad46)") (class "Default")
      (node (ref "IC2") (pin "46") (pinfunction "PC13/ACMP1_CH5/PCNT0_S0IN#0/TIM0_CDTI0#1,3/TIM1_CC0#0_46") (pintype "bidirectional"))
    )
    (net (code "66") (name "unconnected-(IC2C-PC14{slash}ACMP1_CH6{slash}PCNT0_S1IN#0{slash}TIM0_CDTI1#1,3{slash}TIM1_CC1#0-Pad47)") (class "Default")
      (node (ref "IC2") (pin "47") (pinfunction "PC14/ACMP1_CH6/PCNT0_S1IN#0/TIM0_CDTI1#1,3/TIM1_CC1#0_47") (pintype "bidirectional"))
    )
    (net (code "67") (name "unconnected-(IC2C-PC15{slash}ACMP1_CH7{slash}DBG_SWO#1{slash}TIM0_CDTI2#1,3{slash}TIM1_CC2#0-Pad48)") (class "Default")
      (node (ref "IC2") (pin "48") (pinfunction "PC15/ACMP1_CH7/DBG_SWO#1/TIM0_CDTI2#1,3/TIM1_CC2#0_48") (pintype "bidirectional"))
    )
    (net (code "68") (name "unconnected-(IC2D-PD0{slash}ADC0_CH0{slash}PCNT2_S0IN#0{slash}US1_TX#1-Pad28)") (class "Default")
      (node (ref "IC2") (pin "28") (pinfunction "PD0/ADC0_CH0/PCNT2_S0IN#0/US1_TX#1_28") (pintype "bidirectional"))
    )
    (net (code "69") (name "unconnected-(IC2D-PD1{slash}ADC0_CH1{slash}PCNT2_S1IN#0{slash}TIM0_CC0#3{slash}US1_RX#1-Pad29)") (class "Default")
      (node (ref "IC2") (pin "29") (pinfunction "PD1/ADC0_CH1/PCNT2_S1IN#0/TIM0_CC0#3/US1_RX#1_29") (pintype "bidirectional"))
    )
    (net (code "70") (name "unconnected-(IC2D-PD2{slash}ADC0_CH2{slash}TIM0_CC1#3{slash}US1_CLK#1-Pad30)") (class "Default")
      (node (ref "IC2") (pin "30") (pinfunction "PD2/ADC0_CH2/TIM0_CC1#3/US1_CLK#1_30") (pintype "bidirectional"))
    )
    (net (code "71") (name "unconnected-(IC2D-PD5{slash}ADC0_CH5{slash}LEU0_RX#0-Pad33)") (class "Default")
      (node (ref "IC2") (pin "33") (pinfunction "PD5/ADC0_CH5/LEU0_RX#0_33") (pintype "bidirectional"))
    )
    (net (code "72") (name "unconnected-(IC2D-PD7{slash}ADC0_CH7{slash}I2C0_SCL#1{slash}LETIM0_OUT1#0-Pad35)") (class "Default")
      (node (ref "IC2") (pin "35") (pinfunction "PD7/ADC0_CH7/I2C0_SCL#1/LETIM0_OUT1#0_35") (pintype "bidirectional"))
    )
    (net (code "73") (name "unconnected-(IC2D-PD8{slash}CMU_CLK1#1-Pad36)") (class "Default")
      (node (ref "IC2") (pin "36") (pinfunction "PD8/CMU_CLK1#1_36") (pintype "bidirectional"))
    )
    (net (code "74") (name "unconnected-(IC2E-PE8{slash}PCNT2_S0IN#1-Pad56)") (class "Default")
      (node (ref "IC2") (pin "56") (pinfunction "PE8/PCNT2_S0IN#1_56") (pintype "bidirectional"))
    )
    (net (code "75") (name "unconnected-(IC2E-PE9{slash}PCNT2_S1IN#1-Pad57)") (class "Default")
      (node (ref "IC2") (pin "57") (pinfunction "PE9/PCNT2_S1IN#1_57") (pintype "bidirectional"))
    )
    (net (code "76") (name "unconnected-(IC2E-PE13{slash}ACMP0_O{slash}US0_CS#0-Pad61)") (class "Default")
      (node (ref "IC2") (pin "61") (pinfunction "PE13/ACMP0_O/US0_CS#0_61") (pintype "bidirectional"))
    )
    (net (code "77") (name "unconnected-(IC2E-PE14{slash}LEU0_TX#2-Pad62)") (class "Default")
      (node (ref "IC2") (pin "62") (pinfunction "PE14/LEU0_TX#2_62") (pintype "bidirectional"))
    )
    (net (code "78") (name "unconnected-(IC2E-PE15{slash}LEU0_RX#2-Pad63)") (class "Default")
      (node (ref "IC2") (pin "63") (pinfunction "PE15/LEU0_RX#2_63") (pintype "bidirectional"))
    )
    (net (code "79") (name "unconnected-(IC2F-PF3{slash}TIM0_CDTI0#2-Pad52)") (class "Default")
      (node (ref "IC2") (pin "52") (pinfunction "PF3/TIM0_CDTI0#2_52") (pintype "bidirectional"))
    )
    (net (code "80") (name "unconnected-(IC2F-PF4{slash}TIM0_CDTI1#2-Pad53)") (class "Default")
      (node (ref "IC2") (pin "53") (pinfunction "PF4/TIM0_CDTI1#2_53") (pintype "bidirectional"))
    )
    (net (code "81") (name "unconnected-(IC2F-PF5{slash}TIM0_CDTI2#2-Pad54)") (class "Default")
      (node (ref "IC2") (pin "54") (pinfunction "PF5/TIM0_CDTI2#2_54") (pintype "bidirectional"))
    )
    (net (code "82") (name "unconnected-(IC3-PWGD-Pad6)") (class "Default")
      (node (ref "IC3") (pin "6") (pinfunction "PWGD_6") (pintype "output"))
    )
    (net (code "83") (name "unconnected-(X2-Pad7)") (class "Default")
      (node (ref "X2") (pin "7") (pinfunction "7_7") (pintype "passive"))
    )
  )
)
